# Gesture_Sensor.net
KiCad netlist of a schematic drawn in Altium Designer
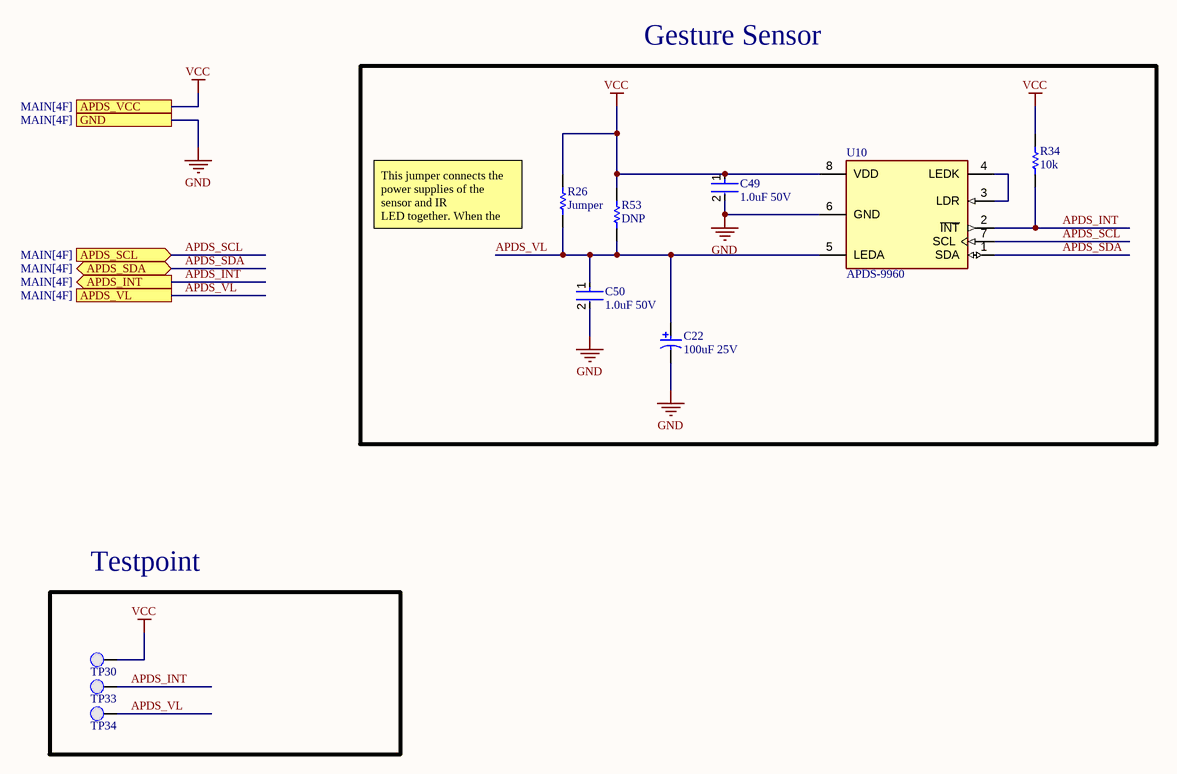
[diagram p0: Gesture_Sensor.SchDoc]

(export (version "E")
  (design (tool "Eeschema 10.0.6"))
  (components
    (comp (ref "C22")
      (value "100uF 25V")
      (footprint "EDK107M025A9HAA")
      (fields (field (name "PARTNUMBER") "UUD1E101MCL1GS") (field (name "MANUFACTURER") "Nichicon"))
      (libsource (lib "Schlib1") (part "CMP-0687-00063-1"))
    )
    (comp (ref "C49")
      (value "1.0uF 50V")
      (footprint "FP-0603-L_1_6_0_1-W_0_8_0-IPC_A")
      (description "None")
      (fields (field (name "TOLERANCE") "10%"))
      (libsource (lib "Altium Content Vault") (part "02cd4be3c70576c341d710602a673aa"))
    )
    (comp (ref "C50")
      (value "1.0uF 50V")
      (footprint "FP-0603-L_1_6_0_1-W_0_8_0-IPC_A")
      (description "None")
      (fields (field (name "TOLERANCE") "10%"))
      (libsource (lib "Altium Content Vault") (part "02cd4be3c70576c341d710602a673aa"))
    )
    (comp (ref "R26")
      (value "Jumper")
      (footprint "RESC0603(1608)_N")
      (description "Jumper 0603 (1608 Metric)")
      (fields (field (name "POWER") "None"))
      (libsource (lib "Altium Content Vault") (part "RES"))
    )
    (comp (ref "R34")
      (value "10k")
      (footprint "RESC1005X40X25ML05T05")
      (description "Chip Resistor, 10 KOhm, +/- 1%, 0.1 W, -55 to 155 degC, 0402 (1005 Metric), RoHS, Tape and Reel")
      (fields (field (name "TOLERANCE") "1%") (field (name "MANUFACTURER") "Panasonic"))
      (libsource (lib "Altium Content Vault") (part "RES-2"))
    )
    (comp (ref "R53") (value "DNP") (footprint "DNP") (libsource (lib "Schlib1") (part "DNP")))
    (comp (ref "TP30")
      (value "0.1\" Pad")
      (footprint "PCBComponent")
      (libsource (lib "Components - 12.02.20 - 18.05") (part "0.1{dblquote} Pad-A.4"))
    )
    (comp (ref "TP33")
      (value "0.1\" Pad")
      (footprint "PCBComponent")
      (libsource (lib "Components - 12.02.20 - 18.05") (part "0.1{dblquote} Pad-A.4"))
    )
    (comp (ref "TP34")
      (value "0.1\" Pad")
      (footprint "PCBComponent")
      (libsource (lib "Components - 12.02.20 - 18.05") (part "0.1{dblquote} Pad-A.4"))
    )
    (comp (ref "U10")
      (value "APDS-9960")
      (footprint "FP-APDS-9960-MFG")
      (description "SENSOR OPT 560NM AMBIENT MODULE")
      (libsource (lib "Schlib1") (part "CMP-2000-05060-2"))
    )
  )
  (nets
    (net (code "1") (name "/APDS_INT") (class "Default")
      (node (ref "R34") (pin "1") (pinfunction "1_1") (pintype "passive"))
      (node (ref "TP33") (pin "1") (pinfunction "PAD_1") (pintype "passive"))
      (node (ref "U10") (pin "2") (pinfunction "~{INT}_2") (pintype "output"))
    )
    (net (code "2") (name "/APDS_SCL") (class "Default")
      (node (ref "U10") (pin "7") (pinfunction "SCL_7") (pintype "input"))
    )
    (net (code "3") (name "/APDS_SDA") (class "Default")
      (node (ref "U10") (pin "1") (pinfunction "SDA_1") (pintype "bidirectional"))
    )
    (net (code "4") (name "/APDS_VL") (class "Default")
      (node (ref "C22") (pin "1") (pinfunction "1_1") (pintype "passive"))
      (node (ref "C50") (pin "1") (pinfunction "1_1") (pintype "passive"))
      (node (ref "R26") (pin "1") (pinfunction "1_1") (pintype "passive"))
      (node (ref "R53") (pin "1") (pinfunction "1_1") (pintype "passive"))
      (node (ref "TP34") (pin "1") (pinfunction "PAD_1") (pintype "passive"))
      (node (ref "U10") (pin "5") (pinfunction "LEDA_5") (pintype "passive"))
    )
    (net (code "5") (name "GND") (class "Default")
      (node (ref "C22") (pin "2") (pinfunction "2_2") (pintype "passive"))
      (node (ref "C49") (pin "2") (pinfunction "2_2") (pintype "passive"))
      (node (ref "C50") (pin "2") (pinfunction "2_2") (pintype "passive"))
      (node (ref "U10") (pin "6") (pinfunction "GND_6") (pintype "power_in"))
    )
    (net (code "6") (name "Net-(U10-LDR)") (class "Default")
      (node (ref "U10") (pin "3") (pinfunction "LDR_3") (pintype "input"))
      (node (ref "U10") (pin "4") (pinfunction "LEDK_4") (pintype "passive"))
    )
    (net (code "7") (name "VCC") (class "Default")
      (node (ref "C49") (pin "1") (pinfunction "1_1") (pintype "passive"))
      (node (ref "R26") (pin "2") (pinfunction "2_2") (pintype "passive"))
      (node (ref "R34") (pin "2") (pinfunction "2_2") (pintype "passive"))
      (node (ref "R53") (pin "2") (pinfunction "2_2") (pintype "passive"))
      (node (ref "TP30") (pin "1") (pinfunction "PAD_1") (pintype "passive"))
      (node (ref "U10") (pin "8") (pinfunction "VDD_8") (pintype "power_in"))
    )
  )
)
